# lab04_2020-11-30_18-55-13.net
KiCad netlist of a schematic drawn in EasyEDA
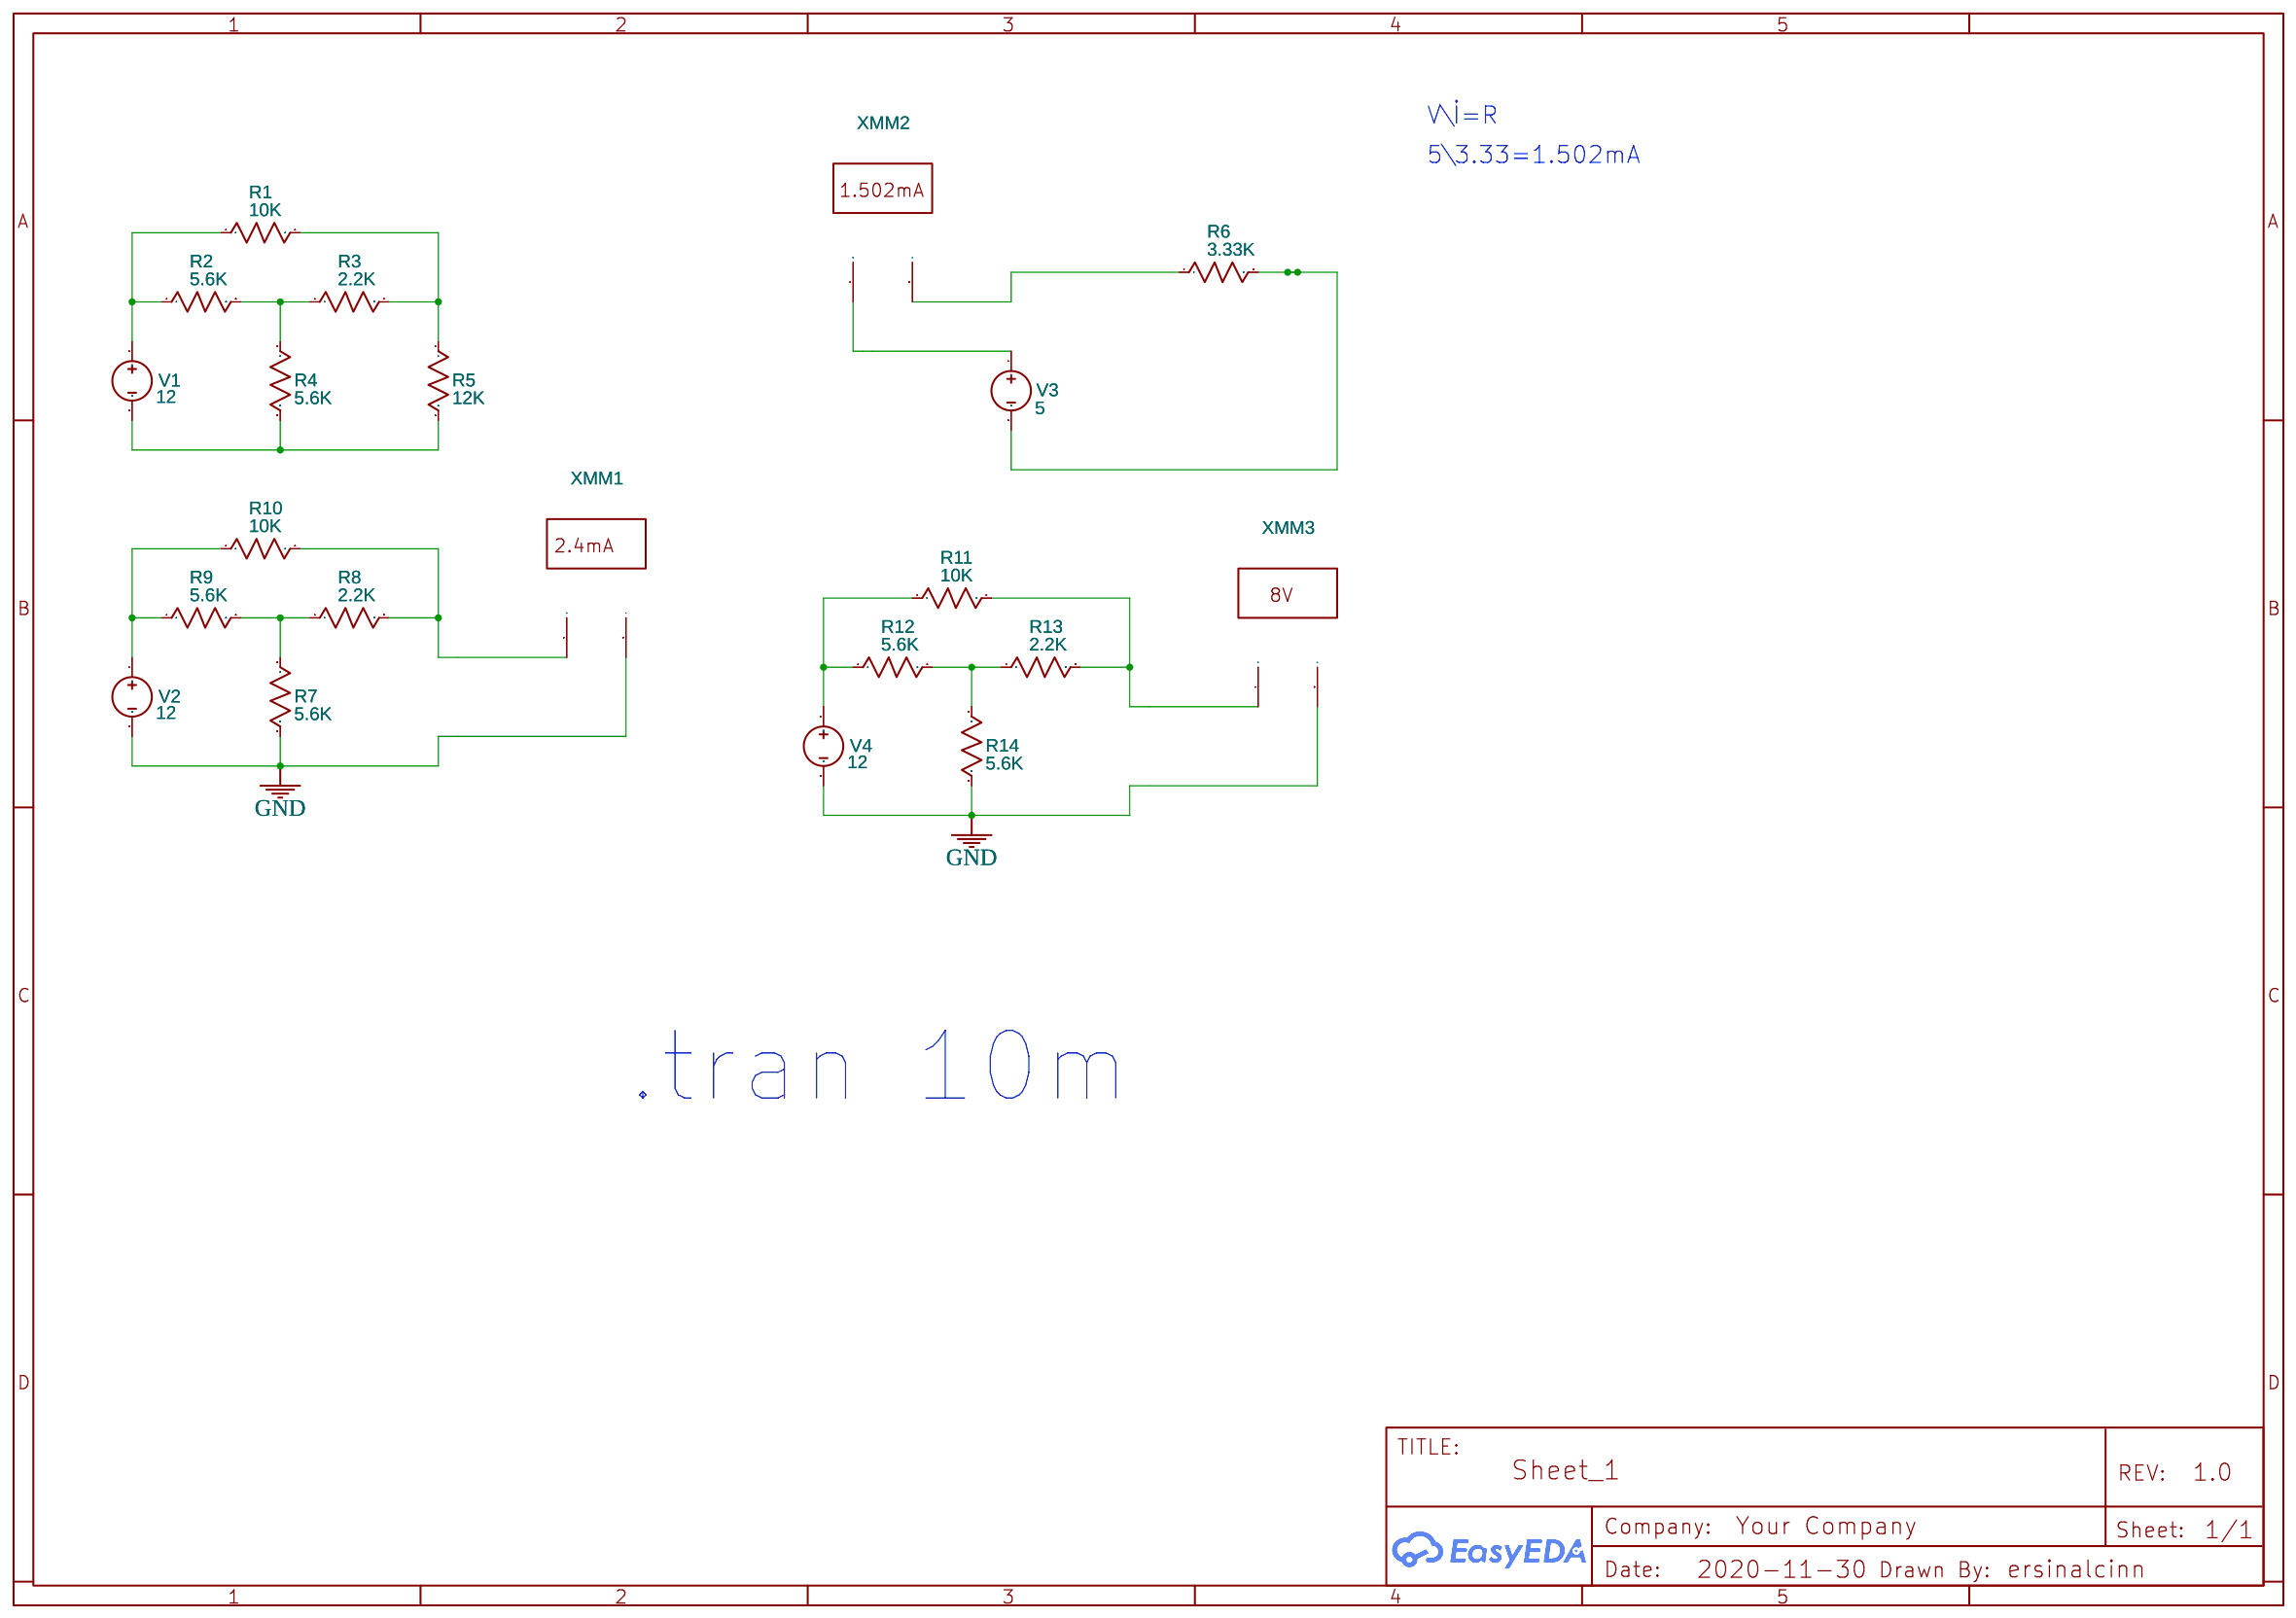
[diagram p0: schematic sheet]

(export (version "E")
  (design (tool "Eeschema 10.0.6"))
  (components
    (comp (ref "R1") (value "10K") (libsource (lib "") (part "Resistor_US_1")))
    (comp (ref "R2") (value "5.6K") (libsource (lib "") (part "Resistor_US_1")))
    (comp (ref "R3") (value "2.2K") (libsource (lib "") (part "Resistor_US_1")))
    (comp (ref "R4") (value "5.6K") (libsource (lib "") (part "Resistor_US")))
    (comp (ref "R5") (value "12K") (libsource (lib "") (part "Resistor_US")))
    (comp (ref "R6") (value "3.33K") (libsource (lib "") (part "Resistor_US_1")))
    (comp (ref "R7") (value "5.6K") (libsource (lib "") (part "Resistor_US")))
    (comp (ref "R8") (value "2.2K") (libsource (lib "") (part "Resistor_US_1")))
    (comp (ref "R9") (value "5.6K") (libsource (lib "") (part "Resistor_US_1")))
    (comp (ref "R10") (value "10K") (libsource (lib "") (part "Resistor_US_1")))
    (comp (ref "R11") (value "10K") (libsource (lib "") (part "Resistor_US_1")))
    (comp (ref "R12") (value "5.6K") (libsource (lib "") (part "Resistor_US_1")))
    (comp (ref "R13") (value "2.2K") (libsource (lib "") (part "Resistor_US_1")))
    (comp (ref "R14") (value "5.6K") (libsource (lib "") (part "Resistor_US")))
    (comp (ref "V1") (value "12") (libsource (lib "") (part "VDC")))
    (comp (ref "V2") (value "12") (libsource (lib "") (part "VDC")))
    (comp (ref "V3") (value "5") (libsource (lib "") (part "VDC")))
    (comp (ref "V4") (value "12") (libsource (lib "") (part "VDC")))
    (comp (ref "XMM1") (value "Multimeter") (libsource (lib "") (part "MULTIMETER")))
    (comp (ref "XMM2") (value "Multimeter") (libsource (lib "") (part "MULTIMETER_1")))
    (comp (ref "XMM3") (value "Multimeter") (libsource (lib "") (part "MULTIMETER_2")))
  )
  (nets
    (net (code "1") (name "GND") (class "Default")
      (node (ref "R14") (pin "2") (pinfunction "2_2") (pintype "unspecified"))
      (node (ref "R7") (pin "2") (pinfunction "2_2") (pintype "unspecified"))
      (node (ref "V2") (pin "2") (pinfunction "2_2") (pintype "unspecified"))
      (node (ref "V4") (pin "2") (pinfunction "2_2") (pintype "unspecified"))
      (node (ref "XMM1") (pin "2") (pinfunction "I_2") (pintype "unspecified"))
      (node (ref "XMM3") (pin "2") (pinfunction "I_2") (pintype "unspecified"))
    )
    (net (code "2") (name "Net-(R1-Pad1)") (class "Default")
      (node (ref "R1") (pin "1") (pinfunction "1_1") (pintype "unspecified"))
      (node (ref "R2") (pin "1") (pinfunction "1_1") (pintype "unspecified"))
      (node (ref "V1") (pin "1") (pinfunction "1_1") (pintype "unspecified"))
    )
    (net (code "3") (name "Net-(R1-Pad2)") (class "Default")
      (node (ref "R1") (pin "2") (pinfunction "2_2") (pintype "unspecified"))
      (node (ref "R3") (pin "2") (pinfunction "2_2") (pintype "unspecified"))
      (node (ref "R5") (pin "1") (pinfunction "1_1") (pintype "unspecified"))
    )
    (net (code "4") (name "Net-(R2-Pad2)") (class "Default")
      (node (ref "R2") (pin "2") (pinfunction "2_2") (pintype "unspecified"))
      (node (ref "R3") (pin "1") (pinfunction "1_1") (pintype "unspecified"))
      (node (ref "R4") (pin "1") (pinfunction "1_1") (pintype "unspecified"))
    )
    (net (code "5") (name "Net-(R4-Pad2)") (class "Default")
      (node (ref "R4") (pin "2") (pinfunction "2_2") (pintype "unspecified"))
      (node (ref "R5") (pin "2") (pinfunction "2_2") (pintype "unspecified"))
      (node (ref "V1") (pin "2") (pinfunction "2_2") (pintype "unspecified"))
    )
    (net (code "6") (name "Net-(R6-Pad2)") (class "Default")
      (node (ref "R6") (pin "2") (pinfunction "2_2") (pintype "unspecified"))
      (node (ref "V3") (pin "2") (pinfunction "2_2") (pintype "unspecified"))
    )
    (net (code "7") (name "Net-(R7-Pad1)") (class "Default")
      (node (ref "R7") (pin "1") (pinfunction "1_1") (pintype "unspecified"))
      (node (ref "R8") (pin "1") (pinfunction "1_1") (pintype "unspecified"))
      (node (ref "R9") (pin "2") (pinfunction "2_2") (pintype "unspecified"))
    )
    (net (code "8") (name "Net-(R10-Pad1)") (class "Default")
      (node (ref "R10") (pin "1") (pinfunction "1_1") (pintype "unspecified"))
      (node (ref "R9") (pin "1") (pinfunction "1_1") (pintype "unspecified"))
      (node (ref "V2") (pin "1") (pinfunction "1_1") (pintype "unspecified"))
    )
    (net (code "9") (name "Net-(R11-Pad1)") (class "Default")
      (node (ref "R11") (pin "1") (pinfunction "1_1") (pintype "unspecified"))
      (node (ref "R12") (pin "1") (pinfunction "1_1") (pintype "unspecified"))
      (node (ref "V4") (pin "1") (pinfunction "1_1") (pintype "unspecified"))
    )
    (net (code "10") (name "Net-(R12-Pad2)") (class "Default")
      (node (ref "R12") (pin "2") (pinfunction "2_2") (pintype "unspecified"))
      (node (ref "R13") (pin "1") (pinfunction "1_1") (pintype "unspecified"))
      (node (ref "R14") (pin "1") (pinfunction "1_1") (pintype "unspecified"))
    )
    (net (code "11") (name "Net-(XMM1-+)") (class "Default")
      (node (ref "R10") (pin "2") (pinfunction "2_2") (pintype "unspecified"))
      (node (ref "R8") (pin "2") (pinfunction "2_2") (pintype "unspecified"))
      (node (ref "XMM1") (pin "1") (pinfunction "+_1") (pintype "unspecified"))
    )
    (net (code "12") (name "Net-(XMM2-+)") (class "Default")
      (node (ref "V3") (pin "1") (pinfunction "1_1") (pintype "unspecified"))
      (node (ref "XMM2") (pin "1") (pinfunction "+_1") (pintype "unspecified"))
    )
    (net (code "13") (name "Net-(XMM2-I)") (class "Default")
      (node (ref "R6") (pin "1") (pinfunction "1_1") (pintype "unspecified"))
      (node (ref "XMM2") (pin "2") (pinfunction "I_2") (pintype "unspecified"))
    )
    (net (code "14") (name "Net-(XMM3-+)") (class "Default")
      (node (ref "R11") (pin "2") (pinfunction "2_2") (pintype "unspecified"))
      (node (ref "R13") (pin "2") (pinfunction "2_2") (pintype "unspecified"))
      (node (ref "XMM3") (pin "1") (pinfunction "+_1") (pintype "unspecified"))
    )
  )
)
